# i2cspilcdbackpack.net
KiCad netlist of a schematic drawn in EAGLE
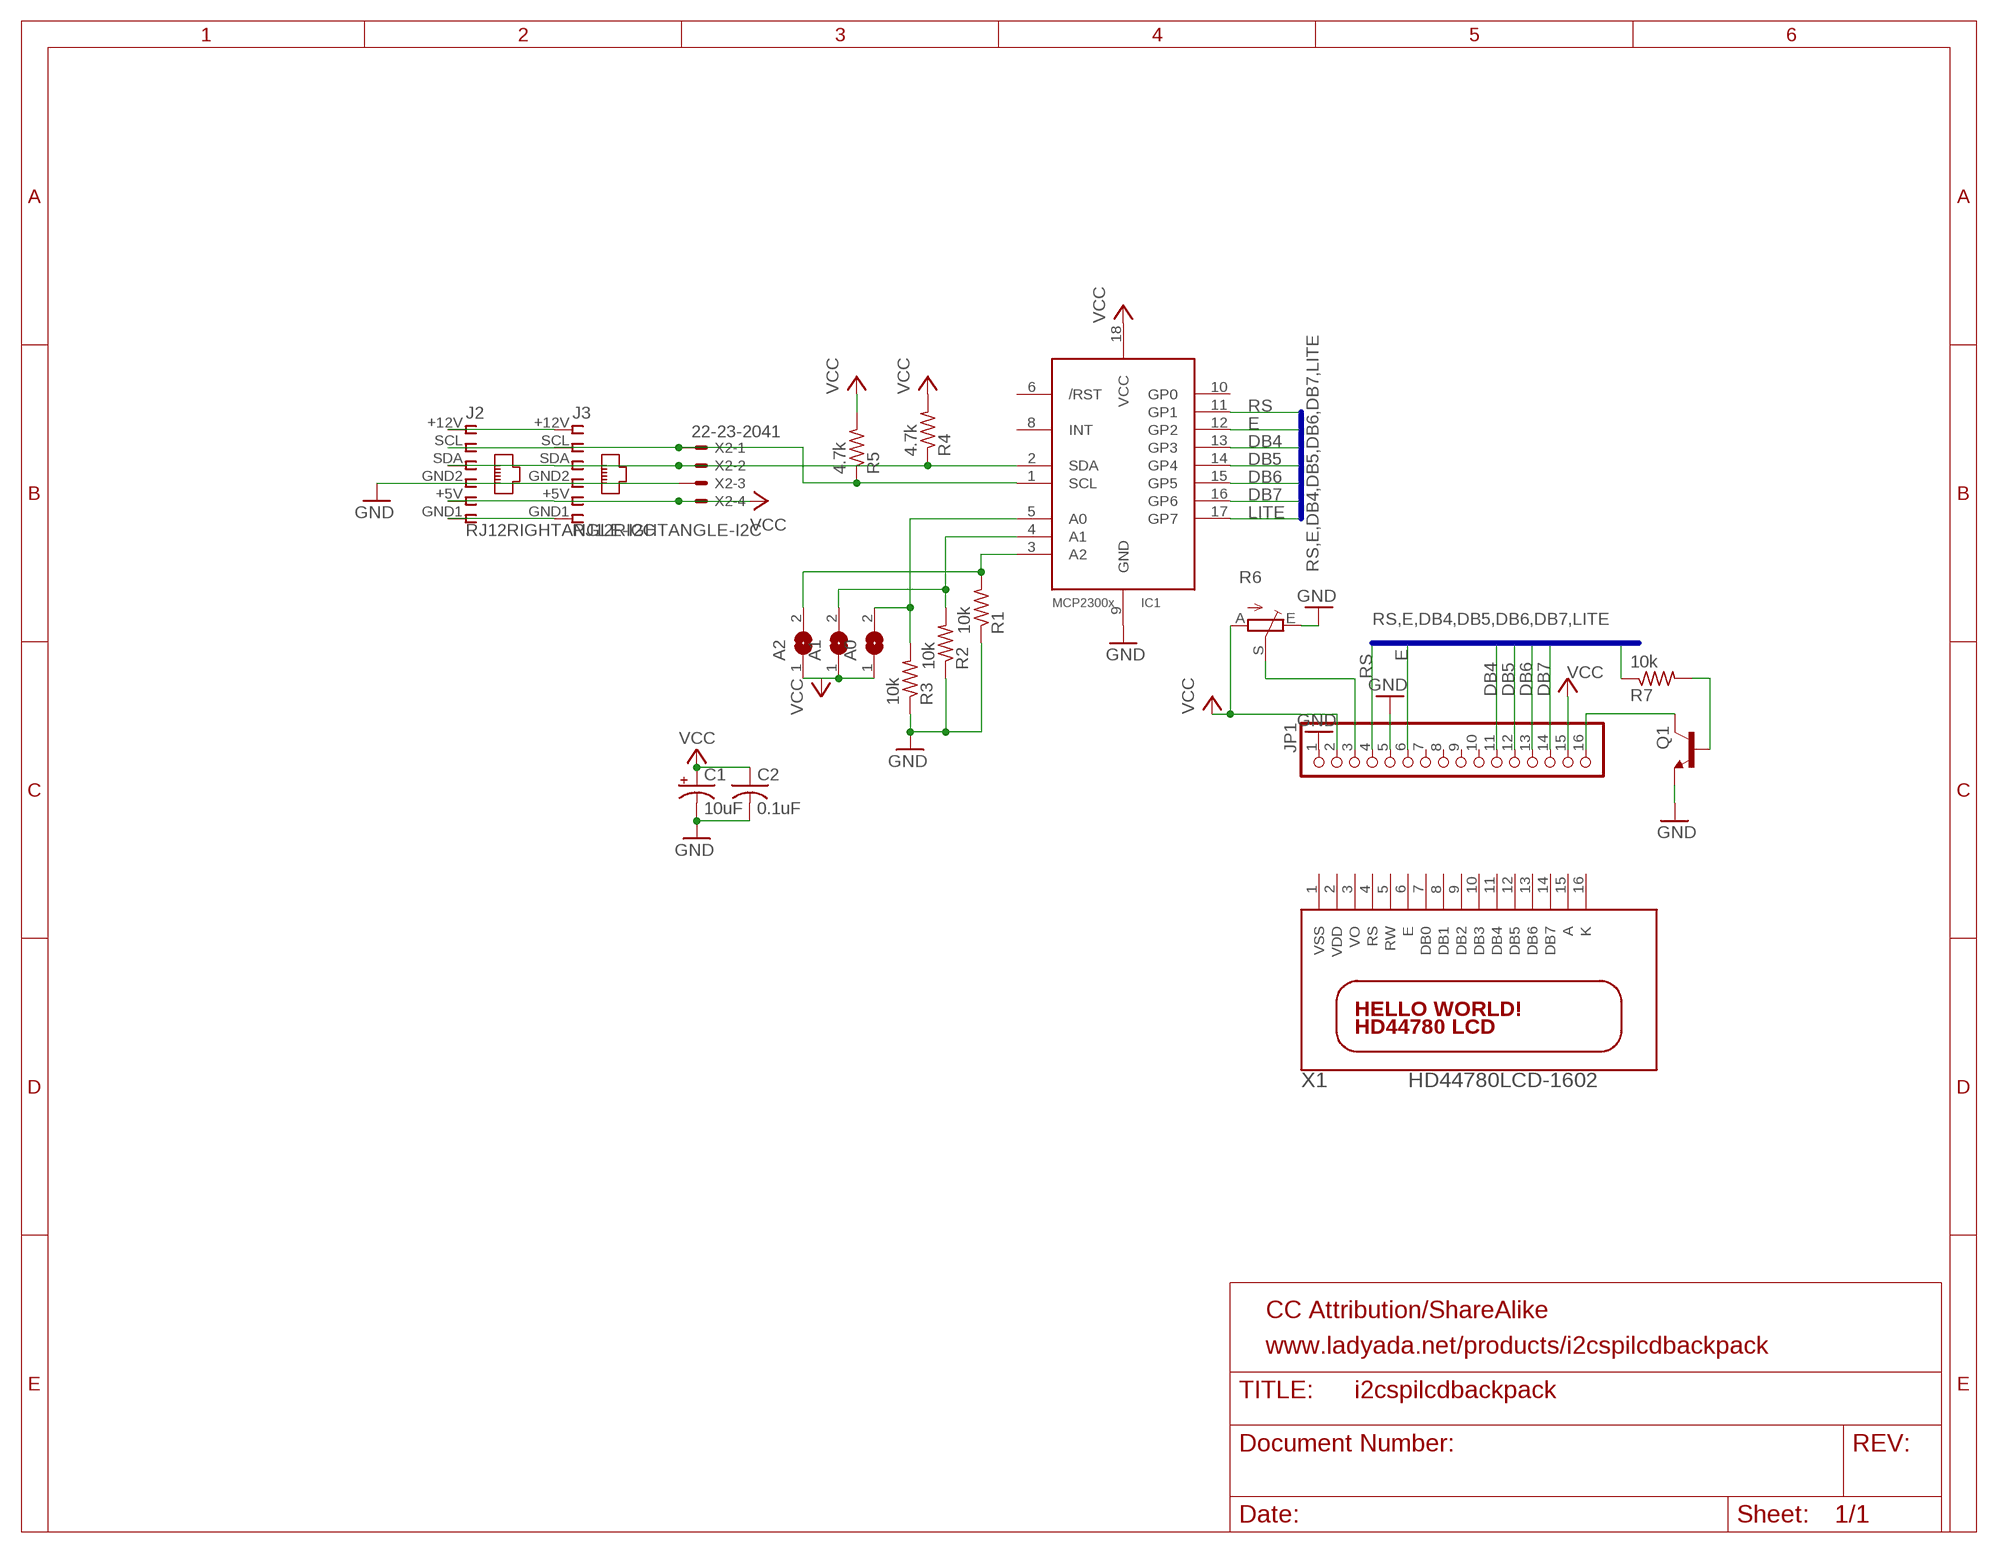
[diagram p0: schematic, sheet 1]

(export (version "E")
  (design (tool "Eeschema 10.0.6"))
  (components
    (comp (ref "A0") (value "SJ") (footprint "eagle-import:SJ") (libsource (lib "eagle-import") (part "SJ")))
    (comp (ref "A1") (value "SJ") (footprint "eagle-import:SJ") (libsource (lib "eagle-import") (part "SJ")))
    (comp (ref "A2") (value "SJ") (footprint "eagle-import:SJ") (libsource (lib "eagle-import") (part "SJ")))
    (comp (ref "C1")
      (value "10uF")
      (footprint "eagle-import:A_3216-18R")
      (libsource (lib "eagle-import") (part "CPOL-USA/3216-18R"))
    )
    (comp (ref "C2")
      (value "0.1uF")
      (footprint "eagle-import:C1206")
      (libsource (lib "eagle-import") (part "C-USC1206"))
    )
    (comp (ref "IC1")
      (value "MCP2300X/P")
      (footprint "eagle-import:DIL18")
      (libsource (lib "eagle-import") (part "MCP2300X/P"))
    )
    (comp (ref "J2")
      (value "RJ12RIGHTANGLE-I2C")
      (footprint "eagle-import:RJ12-RIGHTANGLE-I2C")
      (libsource (lib "eagle-import") (part "RJ12RIGHTANGLE-I2C"))
    )
    (comp (ref "J3")
      (value "RJ12RIGHTANGLE-I2C")
      (footprint "eagle-import:RJ12-RIGHTANGLE-I2C")
      (libsource (lib "eagle-import") (part "RJ12RIGHTANGLE-I2C"))
    )
    (comp (ref "JP1")
      (value "PINHD-1X16")
      (footprint "eagle-import:1X16")
      (libsource (lib "eagle-import") (part "PINHD-1X16"))
    )
    (comp (ref "Q1")
      (value "MMBT2222ALT1-NPN-SOT23-BEC")
      (footprint "eagle-import:SOT23-BEC")
      (libsource (lib "eagle-import") (part "-NPN-SOT23-BECMMBT2222ALT1"))
    )
    (comp (ref "R1")
      (value "10k")
      (footprint "eagle-import:M1206")
      (libsource (lib "eagle-import") (part "R-US_M1206"))
    )
    (comp (ref "R2")
      (value "10k")
      (footprint "eagle-import:M1206")
      (libsource (lib "eagle-import") (part "R-US_M1206"))
    )
    (comp (ref "R3")
      (value "10k")
      (footprint "eagle-import:M1206")
      (libsource (lib "eagle-import") (part "R-US_M1206"))
    )
    (comp (ref "R4")
      (value "4.7k")
      (footprint "eagle-import:M1206")
      (libsource (lib "eagle-import") (part "R-US_M1206"))
    )
    (comp (ref "R5")
      (value "4.7k")
      (footprint "eagle-import:M1206")
      (libsource (lib "eagle-import") (part "R-US_M1206"))
    )
    (comp (ref "R6")
      (value "TRIM_EU-CA9V")
      (footprint "eagle-import:CA9V")
      (libsource (lib "eagle-import") (part "TRIM_EU-CA9V"))
    )
    (comp (ref "R7")
      (value "10k")
      (footprint "eagle-import:M1206")
      (libsource (lib "eagle-import") (part "R-US_M1206"))
    )
    (comp (ref "X1")
      (value "HD44780LCD-1602")
      (footprint "eagle-import:LCD1602")
      (libsource (lib "eagle-import") (part "HD44780LCD-1602"))
    )
    (comp (ref "X2")
      (value "22-23-2041")
      (footprint "eagle-import:22-23-2041")
      (fields (field (name "MF") "MOLEX"))
      (libsource (lib "eagle-import") (part "22-23-2041"))
    )
  )
  (nets
    (net (code "1") (name "/DB4") (class "Default")
      (node (ref "IC1") (pin "13") (pinfunction "GP3_13") (pintype "bidirectional"))
      (node (ref "JP1") (pin "11") (pinfunction "11_11") (pintype "passive"))
    )
    (net (code "2") (name "/DB5") (class "Default")
      (node (ref "IC1") (pin "14") (pinfunction "GP4_14") (pintype "bidirectional"))
      (node (ref "JP1") (pin "12") (pinfunction "12_12") (pintype "passive"))
    )
    (net (code "3") (name "/DB6") (class "Default")
      (node (ref "IC1") (pin "15") (pinfunction "GP5_15") (pintype "bidirectional"))
      (node (ref "JP1") (pin "13") (pinfunction "13_13") (pintype "passive"))
    )
    (net (code "4") (name "/DB7") (class "Default")
      (node (ref "IC1") (pin "16") (pinfunction "GP6_16") (pintype "bidirectional"))
      (node (ref "JP1") (pin "14") (pinfunction "14_14") (pintype "passive"))
    )
    (net (code "5") (name "/E") (class "Default")
      (node (ref "IC1") (pin "12") (pinfunction "GP2_12") (pintype "bidirectional"))
      (node (ref "JP1") (pin "6") (pinfunction "6_6") (pintype "passive"))
    )
    (net (code "6") (name "/LITE") (class "Default")
      (node (ref "IC1") (pin "17") (pinfunction "GP7_17") (pintype "bidirectional"))
      (node (ref "R7") (pin "1") (pinfunction "1_1") (pintype "passive"))
    )
    (net (code "7") (name "/RS") (class "Default")
      (node (ref "IC1") (pin "11") (pinfunction "GP1_11") (pintype "bidirectional"))
      (node (ref "JP1") (pin "4") (pinfunction "4_4") (pintype "passive"))
    )
    (net (code "8") (name "/VDD") (class "Default")
      (node (ref "X1") (pin "2") (pinfunction "VDD_2") (pintype "power_in"))
    )
    (net (code "9") (name "/VSS") (class "Default")
      (node (ref "X1") (pin "1") (pinfunction "VSS_1") (pintype "power_in"))
    )
    (net (code "11") (name "GND") (class "Default")
      (node (ref "C1") (pin "-") (pinfunction "-_-") (pintype "passive"))
      (node (ref "C2") (pin "2") (pinfunction "2_2") (pintype "passive"))
      (node (ref "IC1") (pin "9") (pinfunction "GND_9") (pintype "power_in"))
      (node (ref "J2") (pin "GND2") (pinfunction "4_GND2") (pintype "power_in"))
      (node (ref "J3") (pin "GND2") (pinfunction "4_GND2") (pintype "power_in"))
      (node (ref "JP1") (pin "1") (pinfunction "1_1") (pintype "passive"))
      (node (ref "JP1") (pin "5") (pinfunction "5_5") (pintype "passive"))
      (node (ref "Q1") (pin "E") (pinfunction "E_E") (pintype "passive"))
      (node (ref "R1") (pin "1") (pinfunction "1_1") (pintype "passive"))
      (node (ref "R2") (pin "1") (pinfunction "1_1") (pintype "passive"))
      (node (ref "R3") (pin "1") (pinfunction "1_1") (pintype "passive"))
      (node (ref "R6") (pin "E") (pinfunction "E_E") (pintype "passive"))
      (node (ref "X2") (pin "3") (pinfunction "S_3") (pintype "passive"))
    )
    (net (code "12") (name "Net-(IC1-A0)") (class "Default")
      (node (ref "A0") (pin "2") (pinfunction "2_2") (pintype "passive"))
      (node (ref "IC1") (pin "5") (pinfunction "A0_5") (pintype "input"))
      (node (ref "R3") (pin "2") (pinfunction "2_2") (pintype "passive"))
    )
    (net (code "13") (name "Net-(IC1-A1)") (class "Default")
      (node (ref "A1") (pin "2") (pinfunction "2_2") (pintype "passive"))
      (node (ref "IC1") (pin "4") (pinfunction "A1_4") (pintype "input"))
      (node (ref "R2") (pin "2") (pinfunction "2_2") (pintype "passive"))
    )
    (net (code "14") (name "Net-(IC1-A2)") (class "Default")
      (node (ref "A2") (pin "2") (pinfunction "2_2") (pintype "passive"))
      (node (ref "IC1") (pin "3") (pinfunction "A2_3") (pintype "input"))
      (node (ref "R1") (pin "2") (pinfunction "2_2") (pintype "passive"))
    )
    (net (code "15") (name "Net-(IC1-SCL)") (class "Default")
      (node (ref "IC1") (pin "1") (pinfunction "SCL_1") (pintype "bidirectional"))
      (node (ref "J2") (pin "SCL") (pinfunction "2_SCL") (pintype "bidirectional"))
      (node (ref "J3") (pin "SCL") (pinfunction "2_SCL") (pintype "bidirectional"))
      (node (ref "R5") (pin "1") (pinfunction "1_1") (pintype "passive"))
      (node (ref "X2") (pin "1") (pinfunction "S_1") (pintype "passive"))
    )
    (net (code "16") (name "Net-(IC1-SDA)") (class "Default")
      (node (ref "IC1") (pin "2") (pinfunction "SDA_2") (pintype "bidirectional"))
      (node (ref "J2") (pin "SDA") (pinfunction "3_SDA") (pintype "bidirectional"))
      (node (ref "J3") (pin "SDA") (pinfunction "3_SDA") (pintype "bidirectional"))
      (node (ref "R4") (pin "1") (pinfunction "1_1") (pintype "passive"))
      (node (ref "X2") (pin "2") (pinfunction "S_2") (pintype "passive"))
    )
    (net (code "17") (name "Net-(J2-1)") (class "Default")
      (node (ref "J2") (pin "+12V") (pinfunction "1_+12V") (pintype "power_in"))
      (node (ref "J3") (pin "+12V") (pinfunction "1_+12V") (pintype "power_in"))
    )
    (net (code "18") (name "Net-(J2-6)") (class "Default")
      (node (ref "J2") (pin "GND1") (pinfunction "6_GND1") (pintype "power_in"))
      (node (ref "J3") (pin "GND1") (pinfunction "6_GND1") (pintype "power_in"))
    )
    (net (code "19") (name "Net-(JP1-Pad3)") (class "Default")
      (node (ref "JP1") (pin "3") (pinfunction "3_3") (pintype "passive"))
      (node (ref "R6") (pin "S") (pinfunction "S_S") (pintype "passive"))
    )
    (net (code "20") (name "Net-(JP1-Pad16)") (class "Default")
      (node (ref "JP1") (pin "16") (pinfunction "16_16") (pintype "passive"))
      (node (ref "Q1") (pin "C") (pinfunction "C_C") (pintype "passive"))
    )
    (net (code "21") (name "Net-(Q1-PadB)") (class "Default")
      (node (ref "Q1") (pin "B") (pinfunction "B_B") (pintype "passive"))
      (node (ref "R7") (pin "2") (pinfunction "2_2") (pintype "passive"))
    )
    (net (code "22") (name "VCC") (class "Default")
      (node (ref "A0") (pin "1") (pinfunction "1_1") (pintype "passive"))
      (node (ref "A1") (pin "1") (pinfunction "1_1") (pintype "passive"))
      (node (ref "A2") (pin "1") (pinfunction "1_1") (pintype "passive"))
      (node (ref "C1") (pin "+") (pinfunction "+_+") (pintype "passive"))
      (node (ref "C2") (pin "1") (pinfunction "1_1") (pintype "passive"))
      (node (ref "IC1") (pin "18") (pinfunction "VCC_18") (pintype "power_in"))
      (node (ref "J2") (pin "+5V") (pinfunction "5_+5V") (pintype "power_in"))
      (node (ref "J3") (pin "+5V") (pinfunction "5_+5V") (pintype "power_in"))
      (node (ref "JP1") (pin "15") (pinfunction "15_15") (pintype "passive"))
      (node (ref "JP1") (pin "2") (pinfunction "2_2") (pintype "passive"))
      (node (ref "R4") (pin "2") (pinfunction "2_2") (pintype "passive"))
      (node (ref "R5") (pin "2") (pinfunction "2_2") (pintype "passive"))
      (node (ref "R6") (pin "A") (pinfunction "A_A") (pintype "passive"))
      (node (ref "X2") (pin "4") (pinfunction "S_4") (pintype "passive"))
    )
    (net (code "23") (name "unconnected-(IC1-GP0-Pad10)") (class "Default")
      (node (ref "IC1") (pin "10") (pinfunction "GP0_10") (pintype "bidirectional"))
    )
    (net (code "24") (name "unconnected-(IC1-INT-Pad8)") (class "Default")
      (node (ref "IC1") (pin "8") (pinfunction "INT_8") (pintype "output"))
    )
    (net (code "25") (name "unconnected-(IC1-{slash}RST-Pad6)") (class "Default")
      (node (ref "IC1") (pin "6") (pinfunction "/RST_6") (pintype "input"))
    )
    (net (code "26") (name "unconnected-(JP1-Pad7)") (class "Default")
      (node (ref "JP1") (pin "7") (pinfunction "7_7") (pintype "passive"))
    )
    (net (code "27") (name "unconnected-(JP1-Pad8)") (class "Default")
      (node (ref "JP1") (pin "8") (pinfunction "8_8") (pintype "passive"))
    )
    (net (code "28") (name "unconnected-(JP1-Pad9)") (class "Default")
      (node (ref "JP1") (pin "9") (pinfunction "9_9") (pintype "passive"))
    )
    (net (code "29") (name "unconnected-(JP1-Pad10)") (class "Default")
      (node (ref "JP1") (pin "10") (pinfunction "10_10") (pintype "passive"))
    )
    (net (code "30") (name "unconnected-(X1-A-Pad15)") (class "Default")
      (node (ref "X1") (pin "15") (pinfunction "A_15") (pintype "input"))
    )
    (net (code "31") (name "unconnected-(X1-DB0-Pad7)") (class "Default")
      (node (ref "X1") (pin "7") (pinfunction "DB0_7") (pintype "bidirectional"))
    )
    (net (code "32") (name "unconnected-(X1-DB1-Pad8)") (class "Default")
      (node (ref "X1") (pin "8") (pinfunction "DB1_8") (pintype "bidirectional"))
    )
    (net (code "33") (name "unconnected-(X1-DB2-Pad9)") (class "Default")
      (node (ref "X1") (pin "9") (pinfunction "DB2_9") (pintype "bidirectional"))
    )
    (net (code "34") (name "unconnected-(X1-DB3-Pad10)") (class "Default")
      (node (ref "X1") (pin "10") (pinfunction "DB3_10") (pintype "bidirectional"))
    )
    (net (code "35") (name "unconnected-(X1-DB4-Pad11)") (class "Default")
      (node (ref "X1") (pin "11") (pinfunction "DB4_11") (pintype "bidirectional"))
    )
    (net (code "36") (name "unconnected-(X1-DB5-Pad12)") (class "Default")
      (node (ref "X1") (pin "12") (pinfunction "DB5_12") (pintype "bidirectional"))
    )
    (net (code "37") (name "unconnected-(X1-DB6-Pad13)") (class "Default")
      (node (ref "X1") (pin "13") (pinfunction "DB6_13") (pintype "bidirectional"))
    )
    (net (code "38") (name "unconnected-(X1-DB7-Pad14)") (class "Default")
      (node (ref "X1") (pin "14") (pinfunction "DB7_14") (pintype "bidirectional"))
    )
    (net (code "39") (name "unconnected-(X1-E-Pad6)") (class "Default")
      (node (ref "X1") (pin "6") (pinfunction "E_6") (pintype "input"))
    )
    (net (code "40") (name "unconnected-(X1-K-Pad16)") (class "Default")
      (node (ref "X1") (pin "16") (pinfunction "K_16") (pintype "input"))
    )
    (net (code "41") (name "unconnected-(X1-RS-Pad4)") (class "Default")
      (node (ref "X1") (pin "4") (pinfunction "RS_4") (pintype "input"))
    )
    (net (code "42") (name "unconnected-(X1-RW-Pad5)") (class "Default")
      (node (ref "X1") (pin "5") (pinfunction "RW_5") (pintype "input"))
    )
    (net (code "43") (name "unconnected-(X1-VO-Pad3)") (class "Default")
      (node (ref "X1") (pin "3") (pinfunction "VO_3") (pintype "input"))
    )
  )
)
